# ESP-Live.net
KiCad netlist of a schematic drawn in EAGLE
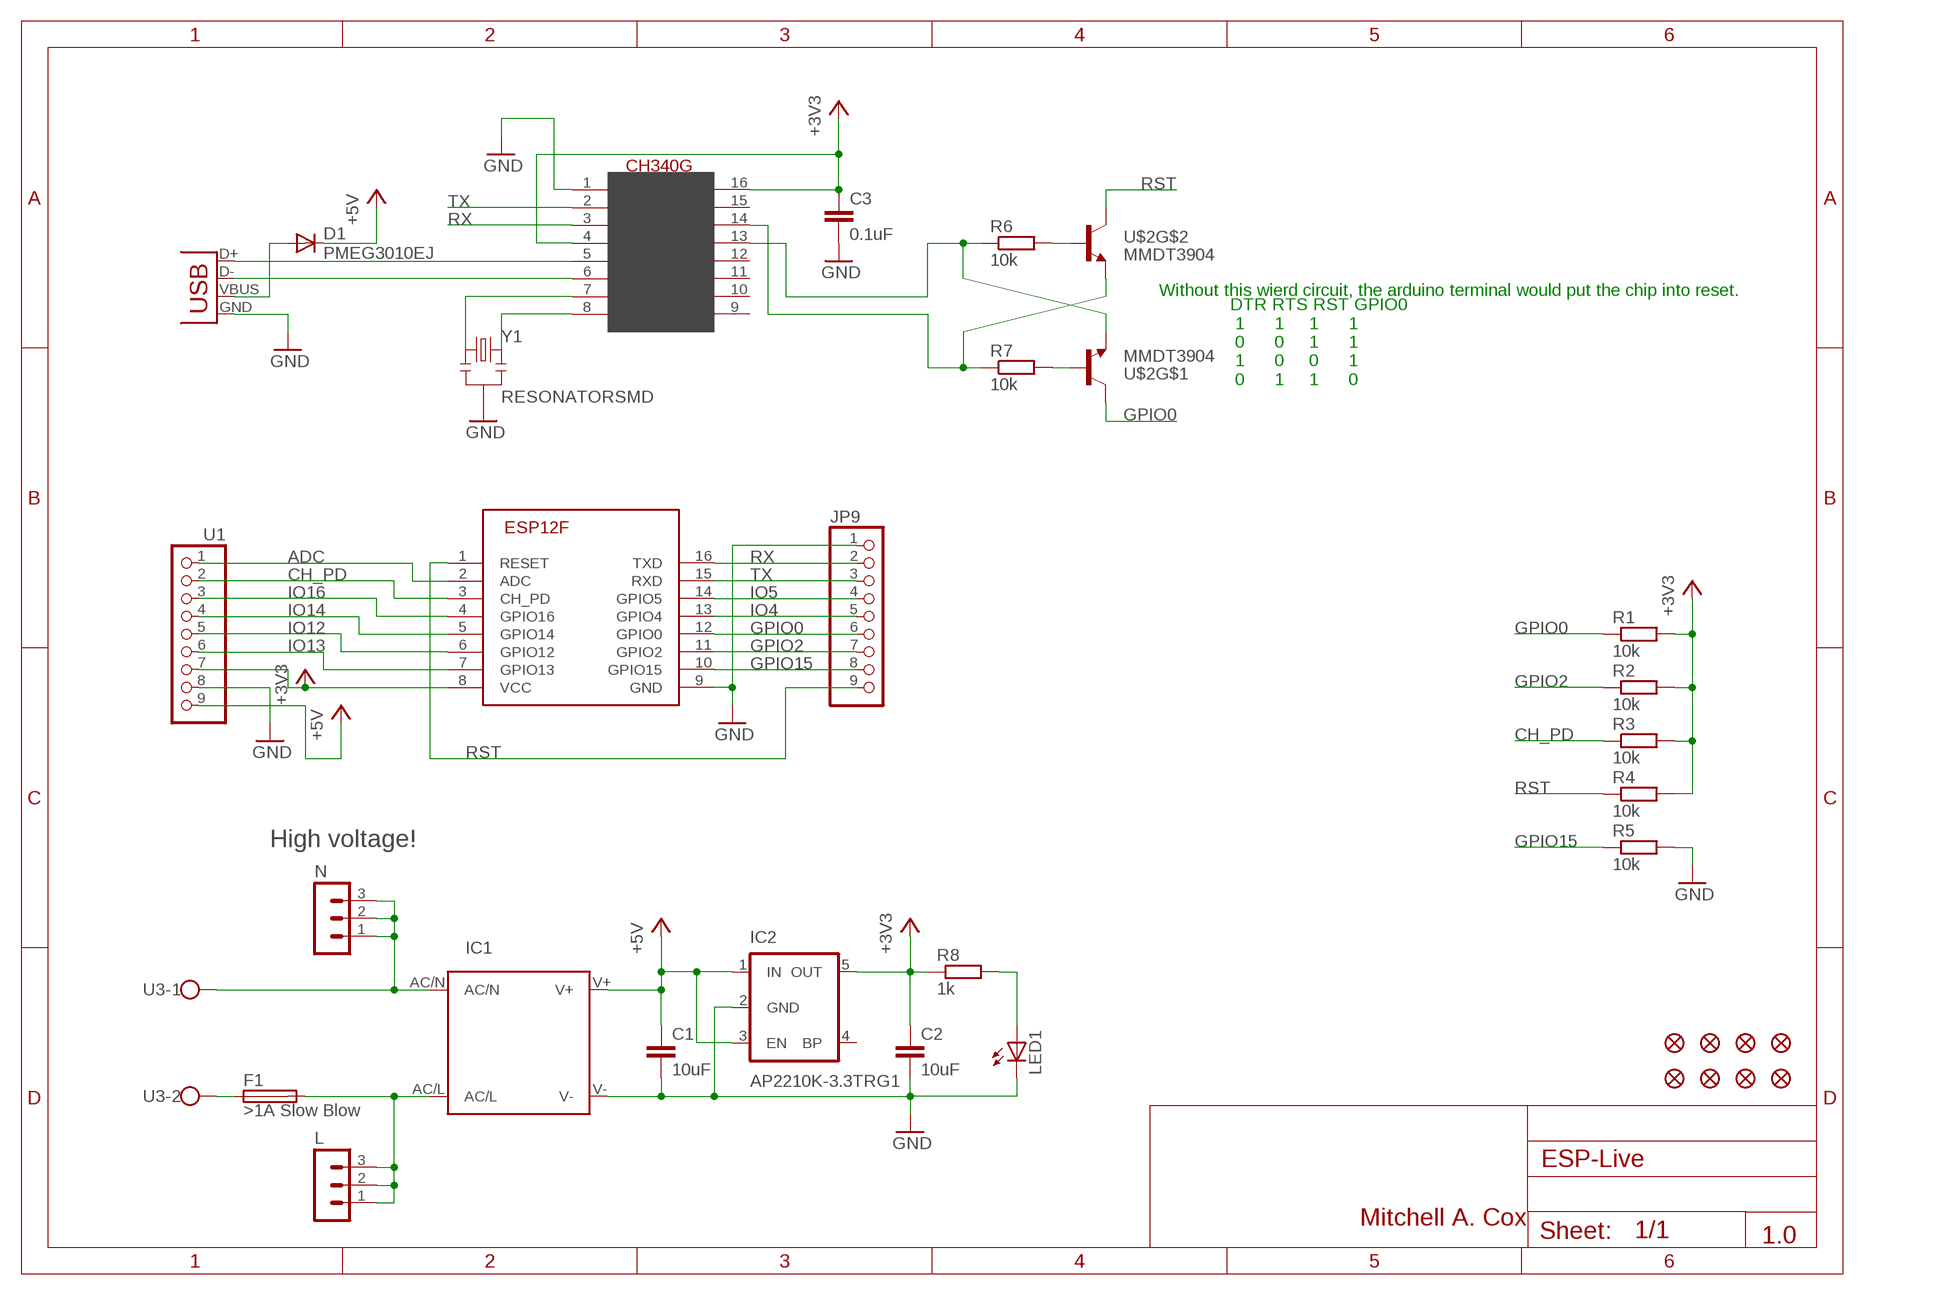
[diagram p0: schematic, sheet 1]

(export (version "E")
  (design (tool "Eeschema 10.0.6"))
  (components
    (comp (ref "C1")
      (value "10uF")
      (footprint "eagle-import:C0805")
      (libsource (lib "eagle-import") (part "C-EUC0805"))
    )
    (comp (ref "C2")
      (value "10uF")
      (footprint "eagle-import:C0805")
      (libsource (lib "eagle-import") (part "C-EUC0805"))
    )
    (comp (ref "C3")
      (value "0.1uF")
      (footprint "eagle-import:C0805")
      (libsource (lib "eagle-import") (part "C-EUC0805"))
    )
    (comp (ref "CN1")
      (value "USBSMD")
      (footprint "eagle-import:USB-MINIB")
      (libsource (lib "eagle-import") (part "USBSMD"))
    )
    (comp (ref "D1")
      (value "PMEG3010EJ")
      (footprint "eagle-import:SOD-323")
      (libsource (lib "eagle-import") (part "DIODESOD"))
    )
    (comp (ref "F1")
      (value ">1A Slow Blow")
      (footprint "eagle-import:TE5")
      (libsource (lib "eagle-import") (part "TE5"))
    )
    (comp (ref "IC1")
      (value "IRM_01/02_SMDIRM_01/02_SMD")
      (footprint "eagle-import:IRM_01_02_SMD")
      (libsource (lib "eagle-import") (part "IRM_01/02_SMDIRM_01/02_SMD"))
    )
    (comp (ref "IC2")
      (value "AP2210K-3.3TRG1")
      (footprint "eagle-import:SOT23-5")
      (libsource (lib "eagle-import") (part "V_REG_LDOSMD"))
    )
    (comp (ref "IC3")
      (value "ESP-12F")
      (footprint "eagle-import:ESP-12F")
      (libsource (lib "eagle-import") (part "ESP-12F"))
    )
    (comp (ref "JP1")
      (value "FIDUCIAL1X2")
      (footprint "eagle-import:FIDUCIAL-1X2")
      (libsource (lib "eagle-import") (part "FIDUCIAL1X2"))
    )
    (comp (ref "JP2")
      (value "FIDUCIAL1X2")
      (footprint "eagle-import:FIDUCIAL-1X2")
      (libsource (lib "eagle-import") (part "FIDUCIAL1X2"))
    )
    (comp (ref "JP3")
      (value "FIDUCIAL1X2")
      (footprint "eagle-import:FIDUCIAL-1X2")
      (libsource (lib "eagle-import") (part "FIDUCIAL1X2"))
    )
    (comp (ref "JP4")
      (value "FIDUCIAL1X2")
      (footprint "eagle-import:FIDUCIAL-1X2")
      (libsource (lib "eagle-import") (part "FIDUCIAL1X2"))
    )
    (comp (ref "JP5")
      (value "FIDUCIAL1X2")
      (footprint "eagle-import:FIDUCIAL-1X2")
      (libsource (lib "eagle-import") (part "FIDUCIAL1X2"))
    )
    (comp (ref "JP6")
      (value "FIDUCIAL1X2")
      (footprint "eagle-import:FIDUCIAL-1X2")
      (libsource (lib "eagle-import") (part "FIDUCIAL1X2"))
    )
    (comp (ref "JP7")
      (value "FIDUCIAL1X2")
      (footprint "eagle-import:FIDUCIAL-1X2")
      (libsource (lib "eagle-import") (part "FIDUCIAL1X2"))
    )
    (comp (ref "JP8")
      (value "FIDUCIAL1X2")
      (footprint "eagle-import:FIDUCIAL-1X2")
      (libsource (lib "eagle-import") (part "FIDUCIAL1X2"))
    )
    (comp (ref "JP9")
      (value "PINHD-1X9")
      (footprint "eagle-import:1X09-BIG")
      (libsource (lib "eagle-import") (part "PINHD-1X9"))
    )
    (comp (ref "L")
      (value "MA03-1")
      (footprint "eagle-import:MA03-1")
      (libsource (lib "eagle-import") (part "MA03-1"))
    )
    (comp (ref "LED1")
      (value "LEDCHIPLED_0805")
      (footprint "eagle-import:CHIPLED_0805")
      (libsource (lib "eagle-import") (part "LEDCHIPLED_0805"))
    )
    (comp (ref "N")
      (value "MA03-1")
      (footprint "eagle-import:MA03-1")
      (libsource (lib "eagle-import") (part "MA03-1"))
    )
    (comp (ref "R1")
      (value "10k")
      (footprint "eagle-import:M0805")
      (libsource (lib "eagle-import") (part "R-EU_M0805"))
    )
    (comp (ref "R2")
      (value "10k")
      (footprint "eagle-import:M0805")
      (libsource (lib "eagle-import") (part "R-EU_M0805"))
    )
    (comp (ref "R3")
      (value "10k")
      (footprint "eagle-import:M0805")
      (libsource (lib "eagle-import") (part "R-EU_M0805"))
    )
    (comp (ref "R4")
      (value "10k")
      (footprint "eagle-import:M0805")
      (libsource (lib "eagle-import") (part "R-EU_M0805"))
    )
    (comp (ref "R5")
      (value "10k")
      (footprint "eagle-import:M0805")
      (libsource (lib "eagle-import") (part "R-EU_M0805"))
    )
    (comp (ref "R6")
      (value "10k")
      (footprint "eagle-import:M0805")
      (libsource (lib "eagle-import") (part "R-EU_M0805"))
    )
    (comp (ref "R7")
      (value "10k")
      (footprint "eagle-import:M0805")
      (libsource (lib "eagle-import") (part "R-EU_M0805"))
    )
    (comp (ref "R8")
      (value "1k")
      (footprint "eagle-import:M0805")
      (libsource (lib "eagle-import") (part "R-EU_M0805"))
    )
    (comp (ref "U$1")
      (value "CH340G")
      (footprint "eagle-import:SOIC16")
      (libsource (lib "eagle-import") (part "CH340G"))
    )
    (comp (ref "U$2")
      (value "MMDT3904")
      (footprint "eagle-import:SOT363")
      (libsource (lib "eagle-import") (part "MMDT3904"))
    )
    (comp (ref "U1")
      (value "PINHD-1X9")
      (footprint "eagle-import:1X09-BIG")
      (libsource (lib "eagle-import") (part "PINHD-1X9"))
    )
    (comp (ref "U3")
      (value "W237-113")
      (footprint "eagle-import:W237-113")
      (libsource (lib "eagle-import") (part "W237-113"))
    )
    (comp (ref "Y1")
      (value "RESONATORSMD")
      (footprint "eagle-import:RESONATOR-SMD")
      (libsource (lib "eagle-import") (part "RESONATORSMD"))
    )
  )
  (nets
    (net (code "1") (name "+3V3") (class "Default")
      (node (ref "C2") (pin "1") (pinfunction "1_1") (pintype "passive"))
      (node (ref "C3") (pin "1") (pinfunction "1_1") (pintype "passive"))
      (node (ref "IC2") (pin "5") (pinfunction "OUT_5") (pintype "passive"))
      (node (ref "IC3") (pin "8") (pinfunction "VCC_8") (pintype "power_in"))
      (node (ref "R1") (pin "2") (pinfunction "2_2") (pintype "passive"))
      (node (ref "R2") (pin "2") (pinfunction "2_2") (pintype "passive"))
      (node (ref "R3") (pin "2") (pinfunction "2_2") (pintype "passive"))
      (node (ref "R4") (pin "2") (pinfunction "2_2") (pintype "passive"))
      (node (ref "R8") (pin "1") (pinfunction "1_1") (pintype "passive"))
      (node (ref "U$1") (pin "16") (pinfunction "VCC_16") (pintype "bidirectional"))
      (node (ref "U$1") (pin "4") (pinfunction "V3_4") (pintype "bidirectional"))
      (node (ref "U1") (pin "7") (pinfunction "7_7") (pintype "passive"))
    )
    (net (code "2") (name "+5V") (class "Default")
      (node (ref "C1") (pin "1") (pinfunction "1_1") (pintype "passive"))
      (node (ref "D1") (pin "1") (pinfunction "C_1") (pintype "passive"))
      (node (ref "IC1") (pin "V+") (pinfunction "V+_V+") (pintype "output"))
      (node (ref "IC2") (pin "1") (pinfunction "IN_1") (pintype "input"))
      (node (ref "IC2") (pin "3") (pinfunction "EN_3") (pintype "input"))
      (node (ref "U1") (pin "9") (pinfunction "9_9") (pintype "passive"))
    )
    (net (code "3") (name "/ADC") (class "Default")
      (node (ref "IC3") (pin "2") (pinfunction "ADC_2") (pintype "passive"))
      (node (ref "U1") (pin "1") (pinfunction "1_1") (pintype "passive"))
    )
    (net (code "4") (name "/CH_PD") (class "Default")
      (node (ref "IC3") (pin "3") (pinfunction "CH_PD_3") (pintype "input"))
      (node (ref "R3") (pin "1") (pinfunction "1_1") (pintype "passive"))
      (node (ref "U1") (pin "2") (pinfunction "2_2") (pintype "passive"))
    )
    (net (code "5") (name "/GPIO0") (class "Default")
      (node (ref "IC3") (pin "12") (pinfunction "GPIO0_12") (pintype "bidirectional"))
      (node (ref "JP9") (pin "6") (pinfunction "6_6") (pintype "passive"))
      (node (ref "R1") (pin "1") (pinfunction "1_1") (pintype "passive"))
      (node (ref "U$2") (pin "3") (pinfunction "C_3") (pintype "passive"))
    )
    (net (code "6") (name "/GPIO2") (class "Default")
      (node (ref "IC3") (pin "11") (pinfunction "GPIO2_11") (pintype "bidirectional"))
      (node (ref "JP9") (pin "7") (pinfunction "7_7") (pintype "passive"))
      (node (ref "R2") (pin "1") (pinfunction "1_1") (pintype "passive"))
    )
    (net (code "7") (name "/GPIO15") (class "Default")
      (node (ref "IC3") (pin "10") (pinfunction "GPIO15_10") (pintype "bidirectional"))
      (node (ref "JP9") (pin "8") (pinfunction "8_8") (pintype "passive"))
      (node (ref "R5") (pin "1") (pinfunction "1_1") (pintype "passive"))
    )
    (net (code "8") (name "/IO4") (class "Default")
      (node (ref "IC3") (pin "13") (pinfunction "GPIO4_13") (pintype "bidirectional"))
      (node (ref "JP9") (pin "5") (pinfunction "5_5") (pintype "passive"))
    )
    (net (code "9") (name "/IO5") (class "Default")
      (node (ref "IC3") (pin "14") (pinfunction "GPIO5_14") (pintype "bidirectional"))
      (node (ref "JP9") (pin "4") (pinfunction "4_4") (pintype "passive"))
    )
    (net (code "10") (name "/IO12") (class "Default")
      (node (ref "IC3") (pin "6") (pinfunction "GPIO12_6") (pintype "bidirectional"))
      (node (ref "U1") (pin "5") (pinfunction "5_5") (pintype "passive"))
    )
    (net (code "11") (name "/IO13") (class "Default")
      (node (ref "IC3") (pin "7") (pinfunction "GPIO13_7") (pintype "bidirectional"))
      (node (ref "U1") (pin "6") (pinfunction "6_6") (pintype "passive"))
    )
    (net (code "12") (name "/IO14") (class "Default")
      (node (ref "IC3") (pin "5") (pinfunction "GPIO14_5") (pintype "bidirectional"))
      (node (ref "U1") (pin "4") (pinfunction "4_4") (pintype "passive"))
    )
    (net (code "13") (name "/IO16") (class "Default")
      (node (ref "IC3") (pin "4") (pinfunction "GPIO16_4") (pintype "bidirectional"))
      (node (ref "U1") (pin "3") (pinfunction "3_3") (pintype "passive"))
    )
    (net (code "14") (name "/RST") (class "Default")
      (node (ref "IC3") (pin "1") (pinfunction "RESET_1") (pintype "input"))
      (node (ref "JP9") (pin "9") (pinfunction "9_9") (pintype "passive"))
      (node (ref "R4") (pin "1") (pinfunction "1_1") (pintype "passive"))
      (node (ref "U$2") (pin "6") (pinfunction "C_6") (pintype "passive"))
    )
    (net (code "15") (name "/RX") (class "Default")
      (node (ref "IC3") (pin "16") (pinfunction "TXD_16") (pintype "output"))
      (node (ref "JP9") (pin "2") (pinfunction "2_2") (pintype "passive"))
      (node (ref "U$1") (pin "3") (pinfunction "RX_3") (pintype "bidirectional"))
    )
    (net (code "16") (name "/TX") (class "Default")
      (node (ref "IC3") (pin "15") (pinfunction "RXD_15") (pintype "input"))
      (node (ref "JP9") (pin "3") (pinfunction "3_3") (pintype "passive"))
      (node (ref "U$1") (pin "2") (pinfunction "TX_2") (pintype "bidirectional"))
    )
    (net (code "17") (name "GND") (class "Default")
      (node (ref "C1") (pin "2") (pinfunction "2_2") (pintype "passive"))
      (node (ref "C2") (pin "2") (pinfunction "2_2") (pintype "passive"))
      (node (ref "C3") (pin "2") (pinfunction "2_2") (pintype "passive"))
      (node (ref "CN1") (pin "GND") (pinfunction "GND_GND") (pintype "bidirectional"))
      (node (ref "IC1") (pin "V-") (pinfunction "V-_V-") (pintype "output"))
      (node (ref "IC2") (pin "2") (pinfunction "GND_2") (pintype "input"))
      (node (ref "IC3") (pin "9") (pinfunction "GND_9") (pintype "power_in"))
      (node (ref "JP9") (pin "1") (pinfunction "1_1") (pintype "passive"))
      (node (ref "LED1") (pin "C") (pinfunction "C_C") (pintype "passive"))
      (node (ref "R5") (pin "2") (pinfunction "2_2") (pintype "passive"))
      (node (ref "U$1") (pin "1") (pinfunction "GND_1") (pintype "bidirectional"))
      (node (ref "U1") (pin "8") (pinfunction "8_8") (pintype "passive"))
      (node (ref "Y1") (pin "2") (pinfunction "2_2") (pintype "passive"))
    )
    (net (code "18") (name "Net-(D1-A)") (class "Default")
      (node (ref "CN1") (pin "VBUS") (pinfunction "VBUS_VBUS") (pintype "bidirectional"))
      (node (ref "D1") (pin "2") (pinfunction "A_2") (pintype "passive"))
    )
    (net (code "19") (name "Net-(F1-Pad2)") (class "Default")
      (node (ref "F1") (pin "2") (pinfunction "2_2") (pintype "passive"))
      (node (ref "IC1") (pin "AC/L") (pinfunction "AC/L_AC/L") (pintype "input"))
      (node (ref "L") (pin "1") (pinfunction "1_1") (pintype "passive"))
      (node (ref "L") (pin "2") (pinfunction "2_2") (pintype "passive"))
      (node (ref "L") (pin "3") (pinfunction "3_3") (pintype "passive"))
    )
    (net (code "20") (name "Net-(LED1-PadA)") (class "Default")
      (node (ref "LED1") (pin "A") (pinfunction "A_A") (pintype "passive"))
      (node (ref "R8") (pin "2") (pinfunction "2_2") (pintype "passive"))
    )
    (net (code "21") (name "Net-(U$1-D+)") (class "Default")
      (node (ref "CN1") (pin "D+") (pinfunction "D+_D+") (pintype "bidirectional"))
      (node (ref "U$1") (pin "5") (pinfunction "D+_5") (pintype "bidirectional"))
    )
    (net (code "22") (name "Net-(U$1-D-)") (class "Default")
      (node (ref "CN1") (pin "D-") (pinfunction "D-_D-") (pintype "bidirectional"))
      (node (ref "U$1") (pin "6") (pinfunction "D-_6") (pintype "bidirectional"))
    )
    (net (code "23") (name "Net-(U$1-DTR)") (class "Default")
      (node (ref "R6") (pin "1") (pinfunction "1_1") (pintype "passive"))
      (node (ref "U$1") (pin "13") (pinfunction "DTR_13") (pintype "bidirectional"))
      (node (ref "U$2") (pin "4") (pinfunction "E_4") (pintype "passive"))
    )
    (net (code "24") (name "Net-(U$1-RTS)") (class "Default")
      (node (ref "R7") (pin "1") (pinfunction "1_1") (pintype "passive"))
      (node (ref "U$1") (pin "14") (pinfunction "RTS_14") (pintype "bidirectional"))
      (node (ref "U$2") (pin "1") (pinfunction "E_1") (pintype "passive"))
    )
    (net (code "25") (name "Net-(U$1-XI)") (class "Default")
      (node (ref "U$1") (pin "7") (pinfunction "XI_7") (pintype "bidirectional"))
      (node (ref "Y1") (pin "1") (pinfunction "1_1") (pintype "passive"))
    )
    (net (code "26") (name "Net-(U$1-XO)") (class "Default")
      (node (ref "U$1") (pin "8") (pinfunction "XO_8") (pintype "bidirectional"))
      (node (ref "Y1") (pin "3") (pinfunction "3_3") (pintype "passive"))
    )
    (net (code "27") (name "Net-(U$2A-B)") (class "Default")
      (node (ref "R7") (pin "2") (pinfunction "2_2") (pintype "passive"))
      (node (ref "U$2") (pin "5") (pinfunction "B_5") (pintype "passive"))
    )
    (net (code "28") (name "Net-(U$2B-B)") (class "Default")
      (node (ref "R6") (pin "2") (pinfunction "2_2") (pintype "passive"))
      (node (ref "U$2") (pin "2") (pinfunction "B_2") (pintype "passive"))
    )
    (net (code "29") (name "Net-(U3A-KL)") (class "Default")
      (node (ref "IC1") (pin "AC/N") (pinfunction "AC/N_AC/N") (pintype "input"))
      (node (ref "N") (pin "1") (pinfunction "1_1") (pintype "passive"))
      (node (ref "N") (pin "2") (pinfunction "2_2") (pintype "passive"))
      (node (ref "N") (pin "3") (pinfunction "3_3") (pintype "passive"))
      (node (ref "U3") (pin "1") (pinfunction "KL_1") (pintype "passive"))
    )
    (net (code "30") (name "Net-(U3B-KL)") (class "Default")
      (node (ref "F1") (pin "1") (pinfunction "1_1") (pintype "passive"))
      (node (ref "U3") (pin "2") (pinfunction "KL_2") (pintype "passive"))
    )
    (net (code "31") (name "unconnected-(IC2-BP-Pad4)") (class "Default")
      (node (ref "IC2") (pin "4") (pinfunction "BP_4") (pintype "input"))
    )
    (net (code "32") (name "unconnected-(U$1-CTS-Pad9)") (class "Default")
      (node (ref "U$1") (pin "9") (pinfunction "CTS_9") (pintype "bidirectional"))
    )
    (net (code "33") (name "unconnected-(U$1-DCD-Pad12)") (class "Default")
      (node (ref "U$1") (pin "12") (pinfunction "DCD_12") (pintype "bidirectional"))
    )
    (net (code "34") (name "unconnected-(U$1-DSR-Pad10)") (class "Default")
      (node (ref "U$1") (pin "10") (pinfunction "DSR_10") (pintype "bidirectional"))
    )
    (net (code "35") (name "unconnected-(U$1-RI-Pad11)") (class "Default")
      (node (ref "U$1") (pin "11") (pinfunction "RI_11") (pintype "bidirectional"))
    )
    (net (code "36") (name "unconnected-(U$1-RS232-Pad15)") (class "Default")
      (node (ref "U$1") (pin "15") (pinfunction "RS232_15") (pintype "bidirectional"))
    )
  )
)
